# Drone.net
KiCad netlist of a schematic drawn in Altium Designer
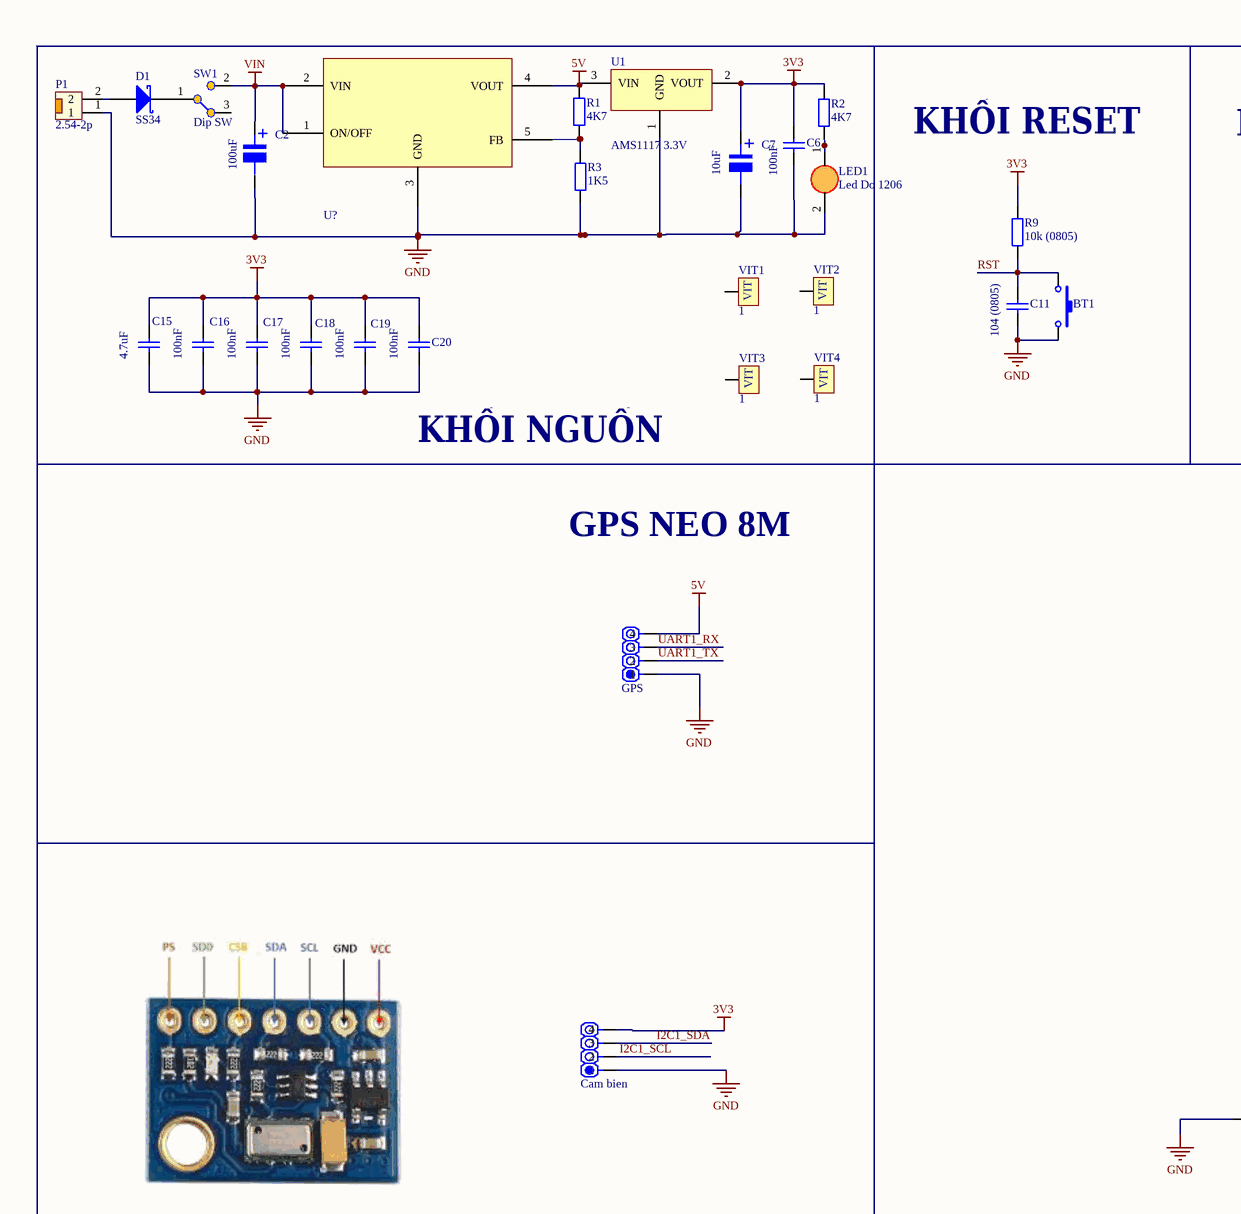
[diagram p0: Drone.SchDoc, top left]
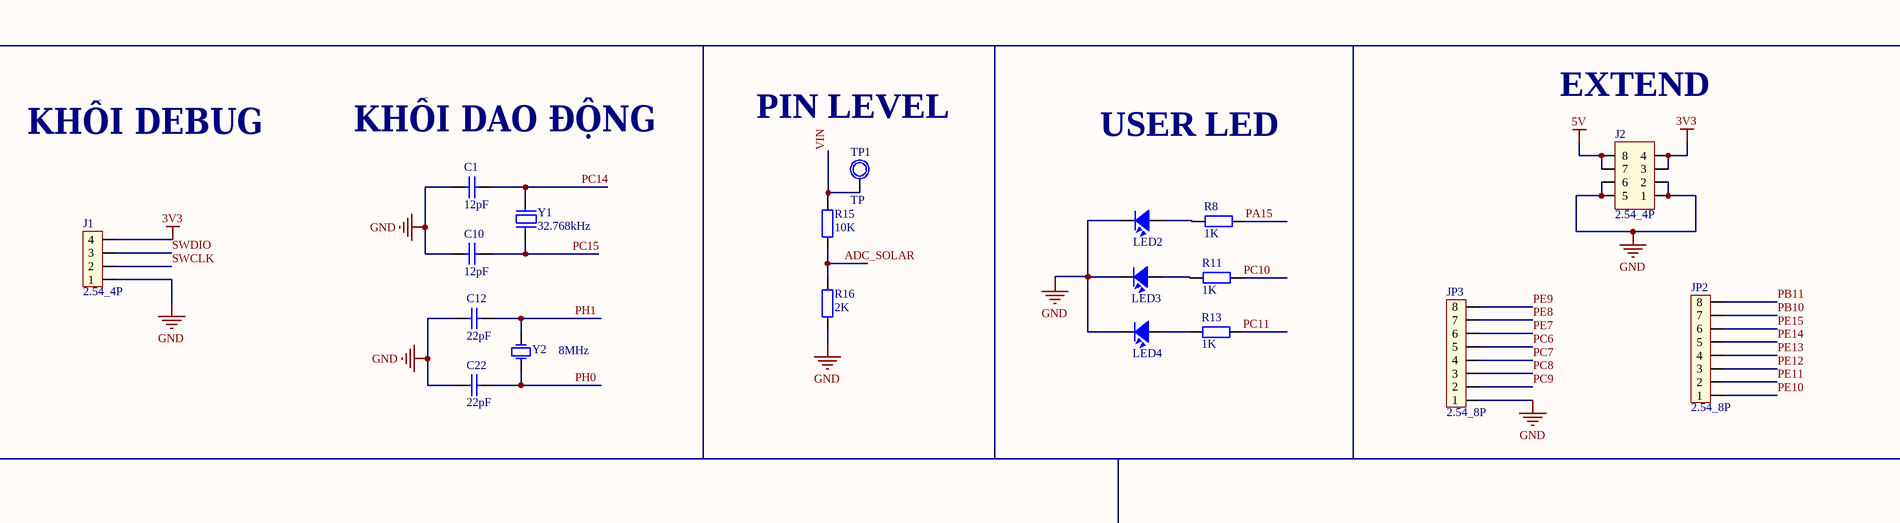
[diagram p1: Drone.SchDoc, top right]
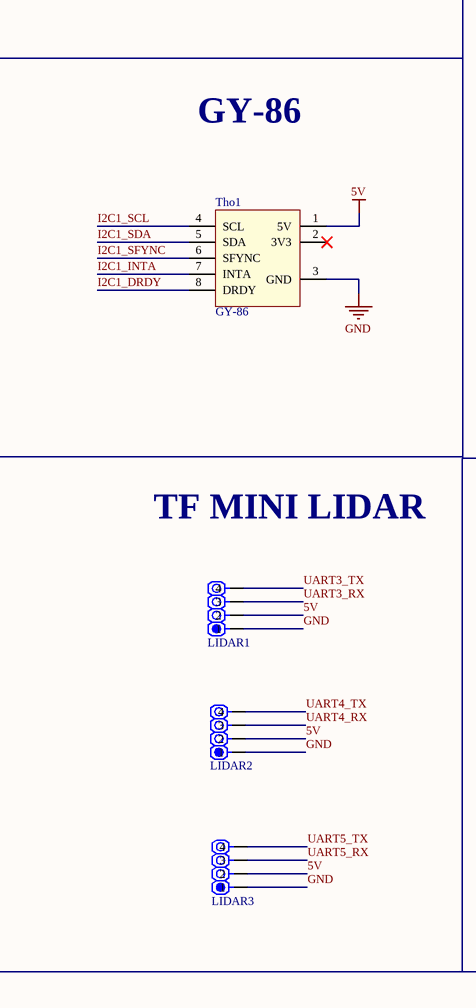
[diagram p2: Drone.SchDoc, bottom left]
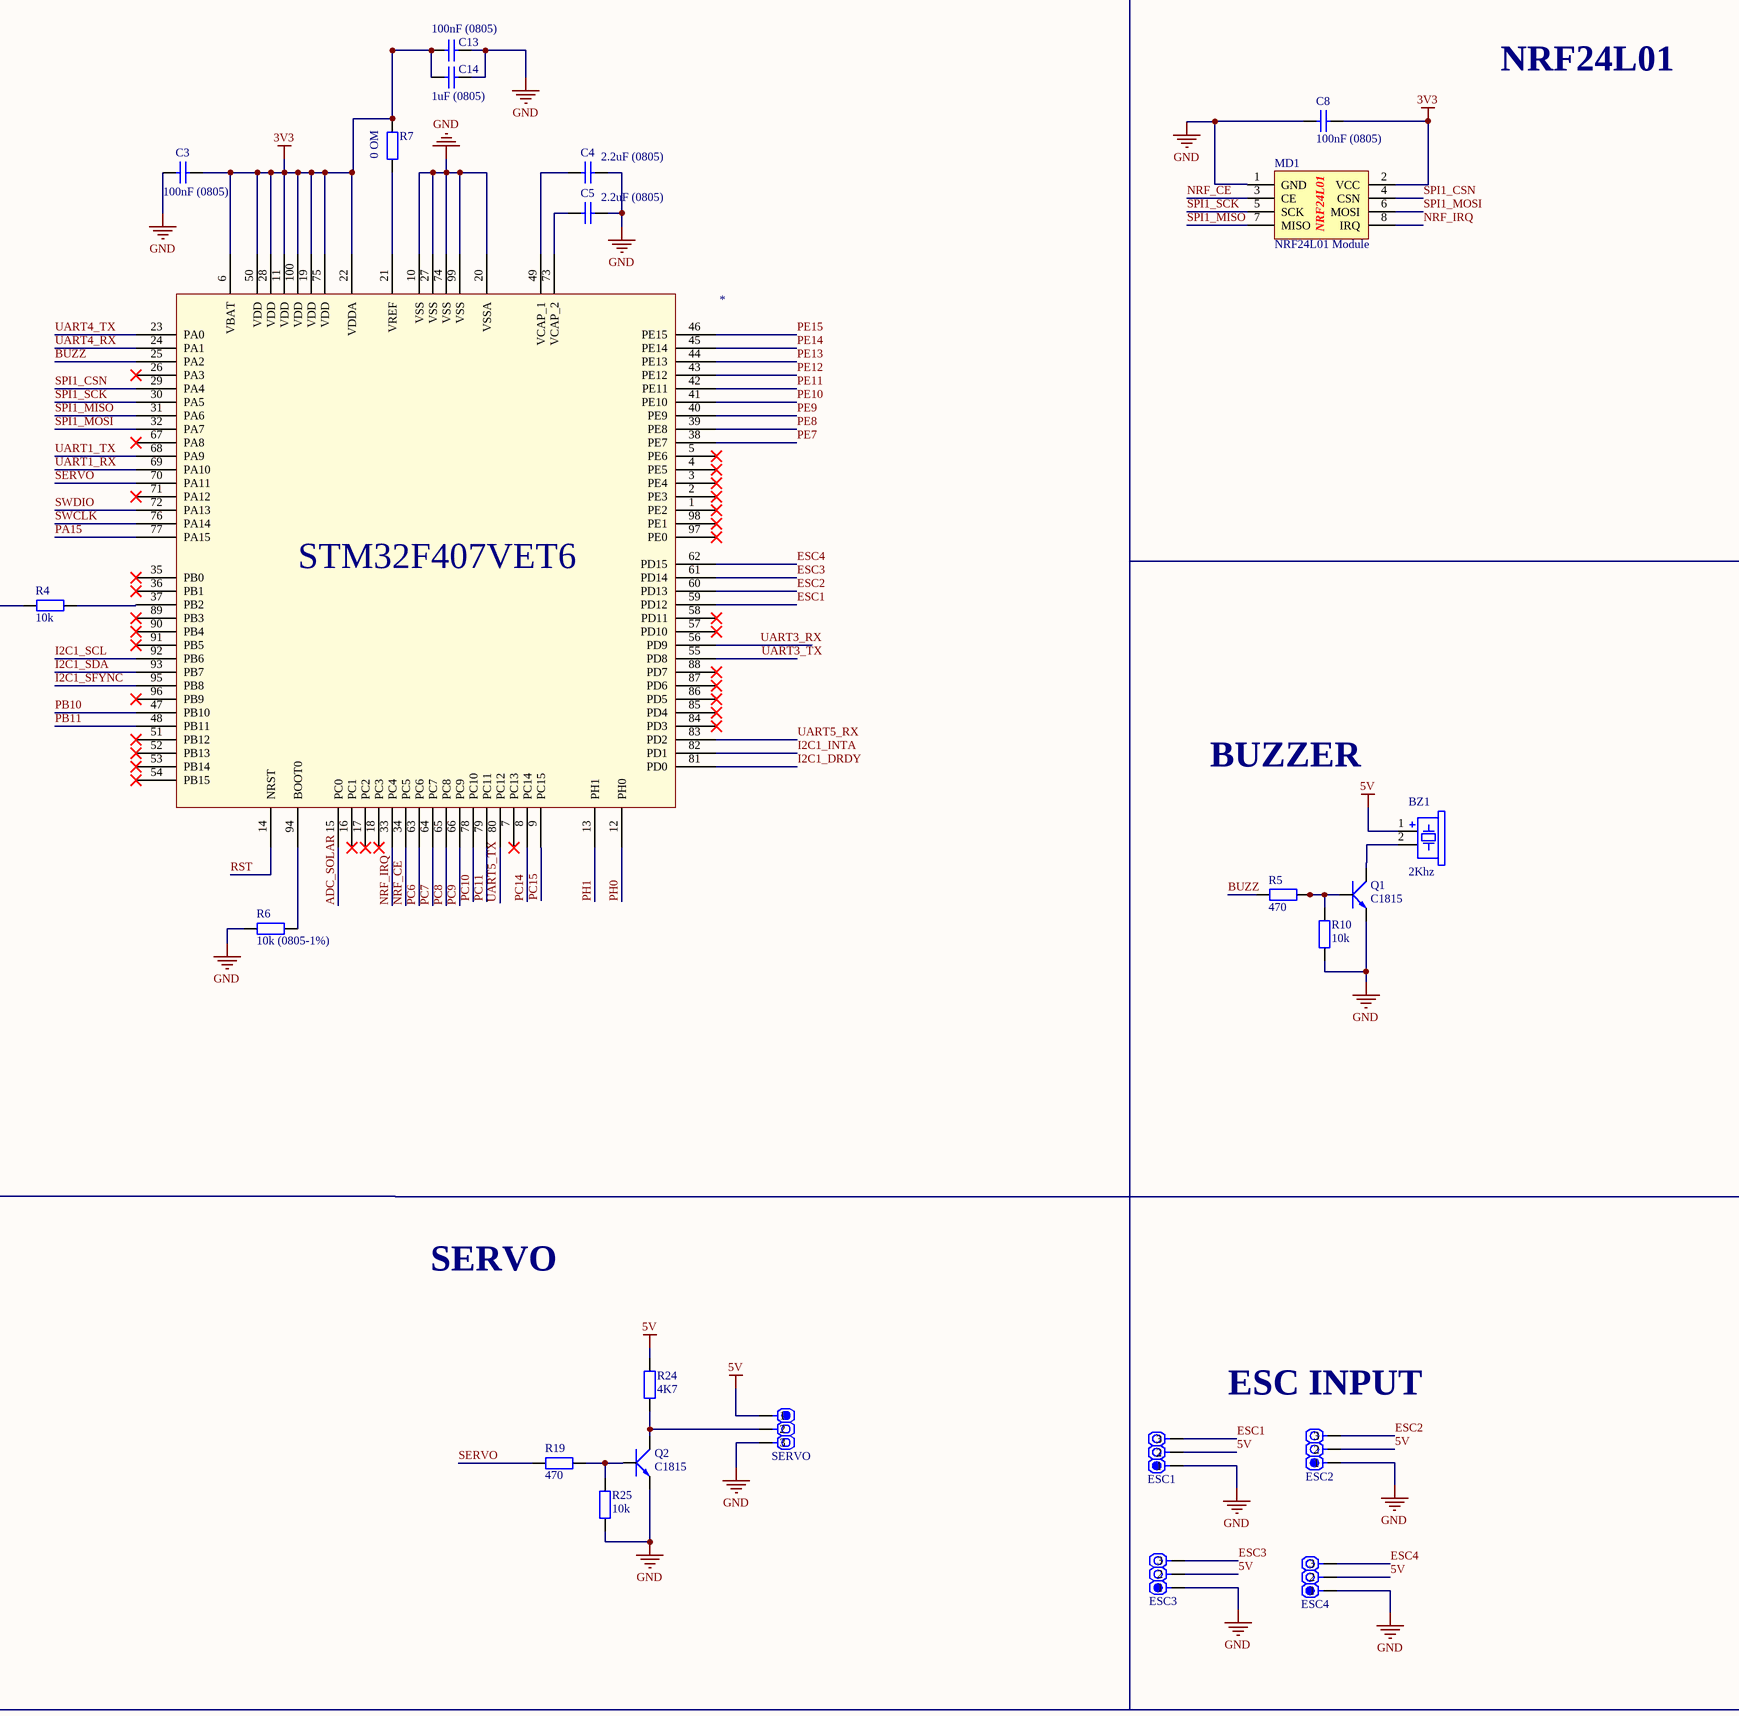
[diagram p3: Drone.SchDoc, bottom right]

(export (version "E")
  (design (tool "Eeschema 10.0.6"))
  (components
    (comp (ref "*")
      (value "STM32F407")
      (footprint "STM32F407Vet6")
      (libsource (lib "STM32f407") (part "STM32F407"))
    )
    (comp (ref "BT1")
      (value "Nút Nhấn 2 Chân 3x6x2.5MM SMD")
      (footprint "Nut Nhan 2 Chan SMD_N")
      (description "Dán")
      (libsource (lib "SCH Chuan") (part "Nut Nhan 2 Chan SMD"))
    )
    (comp (ref "BZ1")
      (value "2Khz")
      (footprint "coi xung")
      (description "Cắm")
      (libsource (lib "SCH Chuan") (part "Coi xung 2Khz"))
    )
    (comp (ref "C1")
      (value "12pF")
      (footprint "tu 0805")
      (description "Dán")
      (libsource (lib "SCH Chuan") (part "Tu 0805 10pF 50V 10%"))
    )
    (comp (ref "C2")
      (value "100uF")
      (footprint "tu nhom 10 (g)")
      (description "Dán")
      (libsource (lib "NhomLib") (part "Tu Nhom 100uF 35V"))
    )
    (comp (ref "C3")
      (value "100nF (0805)")
      (footprint "tu 0805")
      (description "Dán")
      (libsource (lib "SCH Chuan") (part "Tu 0805 220nF 50V 10%"))
    )
    (comp (ref "C4")
      (value "2.2uF (0805)")
      (footprint "tu 0805")
      (description "Dán")
      (libsource (lib "SCH Chuan") (part "Tu 0805 220nF 50V 10%"))
    )
    (comp (ref "C5")
      (value "2.2uF (0805)")
      (footprint "tu 0805")
      (description "Dán")
      (libsource (lib "SCH Chuan") (part "Tu 0805 220nF 50V 10%"))
    )
    (comp (ref "C6")
      (value "100nF")
      (footprint "tu 0805")
      (description "Dán")
      (libsource (lib "NhomLib") (part "Tu 0805 220nF 50V 10%"))
    )
    (comp (ref "C7")
      (value "10uF")
      (footprint "tu nhom 4 (b)")
      (description "Dán")
      (libsource (lib "NhomLib") (part "Tu Nhom 10uF 16V"))
    )
    (comp (ref "C8")
      (value "100nF (0805)")
      (footprint "tu 0805")
      (description "Dán")
      (libsource (lib "SCH Chuan") (part "Tu 0805 220nF 50V 10%"))
    )
    (comp (ref "C10")
      (value "12pF")
      (footprint "tu 0805")
      (description "Dán")
      (libsource (lib "SCH Chuan") (part "Tu 0805 10pF 50V 10%"))
    )
    (comp (ref "C11")
      (value "104 (0805)")
      (footprint "tu 0805")
      (description "Dán")
      (libsource (lib "SCH Chuan") (part "Tu 0805 104 50V 10%"))
    )
    (comp (ref "C12")
      (value "22pF")
      (footprint "tu 0805")
      (description "Dán")
      (libsource (lib "SCH Chuan") (part "Tu 0805 10pF 50V 10%"))
    )
    (comp (ref "C13")
      (value "100nF (0805)")
      (footprint "tu 0805")
      (description "Dán")
      (libsource (lib "SCH Chuan") (part "Tu 0805 220nF 50V 10%"))
    )
    (comp (ref "C14")
      (value "1uF (0805)")
      (footprint "tu 0805")
      (description "Dán")
      (libsource (lib "SCH Chuan") (part "Tu 0805 220nF 50V 10%"))
    )
    (comp (ref "C15")
      (value "4.7uF")
      (footprint "tu 0805")
      (description "Dán")
      (libsource (lib "SCH Chuan") (part "Tu 0805 104 50V 10%"))
    )
    (comp (ref "C16")
      (value "100nF")
      (footprint "tu 0805")
      (description "Dán")
      (libsource (lib "SCH Chuan") (part "Tu 0805 104 50V 10%"))
    )
    (comp (ref "C17")
      (value "100nF")
      (footprint "tu 0805")
      (description "Dán")
      (libsource (lib "SCH Chuan") (part "Tu 0805 104 50V 10%"))
    )
    (comp (ref "C18")
      (value "100nF")
      (footprint "tu 0805")
      (description "Dán")
      (libsource (lib "SCH Chuan") (part "Tu 0805 104 50V 10%"))
    )
    (comp (ref "C19")
      (value "100nF")
      (footprint "tu 0805")
      (description "Dán")
      (libsource (lib "SCH Chuan") (part "Tu 0805 104 50V 10%"))
    )
    (comp (ref "C20")
      (value "100nF")
      (footprint "tu 0805")
      (description "Dán")
      (libsource (lib "SCH Chuan") (part "Tu 0805 104 50V 10%"))
    )
    (comp (ref "C22")
      (value "22pF")
      (footprint "tu 0805")
      (description "Dán")
      (libsource (lib "SCH Chuan") (part "Tu 0805 10pF 50V 10%"))
    )
    (comp (ref "Cam bien")
      (value "IO")
      (footprint "CON.HDR1X4L")
      (description "Header 1x4")
      (fields (field (name "PUBLISHER") "NKIM"))
      (libsource (lib "VPMyLibrary") (part "CON.HDR1x4"))
    )
    (comp (ref "D1")
      (value "SS34")
      (footprint "DIODE_DO214AC_SMA")
      (description "DIODE SCHOTTKY 40V 3A SMA")
      (libsource (lib "NhomLib") (part "SS34"))
    )
    (comp (ref "ESC1")
      (value "IO")
      (footprint "CON.HDR1X3")
      (description "Header 1x3")
      (fields (field (name "PUBLISHER") "NKIM"))
      (libsource (lib "VPMyLibrary") (part "CON.HDR1x3"))
    )
    (comp (ref "ESC2")
      (value "IO")
      (footprint "CON.HDR1X3")
      (description "Header 1x3")
      (fields (field (name "PUBLISHER") "NKIM"))
      (libsource (lib "VPMyLibrary") (part "CON.HDR1x3"))
    )
    (comp (ref "ESC3")
      (value "IO")
      (footprint "CON.HDR1X3")
      (description "Header 1x3")
      (fields (field (name "PUBLISHER") "NKIM"))
      (libsource (lib "VPMyLibrary") (part "CON.HDR1x3"))
    )
    (comp (ref "ESC4")
      (value "IO")
      (footprint "CON.HDR1X3")
      (description "Header 1x3")
      (fields (field (name "PUBLISHER") "NKIM"))
      (libsource (lib "VPMyLibrary") (part "CON.HDR1x3"))
    )
    (comp (ref "GPS")
      (value "IO")
      (footprint "CON.HDR1X4L")
      (description "Header 1x4")
      (fields (field (name "PUBLISHER") "NKIM"))
      (libsource (lib "VPMyLibrary") (part "CON.HDR1x4"))
    )
    (comp (ref "J1")
      (value "2.54_4P")
      (footprint "jump don duc thang 2.54_4p")
      (description "Cắm")
      (libsource (lib "NhomLib") (part "Jump Don Duc Thang 2.54_4P"))
    )
    (comp (ref "J2")
      (value "2.54_4P")
      (footprint "JP4x2")
      (description "Cắm")
      (libsource (lib "NhomLib") (part "Jump Doi Duc 2.54_4Px2"))
    )
    (comp (ref "JP2")
      (value "2.54_8P")
      (footprint "Jump Don Duc Thang 2.54_8p")
      (description "Cắm")
      (libsource (lib "NhomLib") (part "Jump Don Duc 2.54_8P"))
    )
    (comp (ref "JP3")
      (value "2.54_8P")
      (footprint "Jump Don Duc Thang 2.54_8p")
      (description "Cắm")
      (libsource (lib "NhomLib") (part "Jump Don Duc 2.54_8P"))
    )
    (comp (ref "LED1")
      (value "Led Do 1206")
      (footprint "led 1206")
      (description "Dán")
      (libsource (lib "NhomLib") (part "Led 1206 Do"))
    )
    (comp (ref "LED2")
      (value "LED SMD")
      (footprint "SM-LED-0805-Yellow")
      (libsource (lib "syhaunguyen") (part "LED-SMD-0805"))
    )
    (comp (ref "LED3")
      (value "LED SMD")
      (footprint "SM-LED-0805-Green")
      (libsource (lib "syhaunguyen") (part "LED-SMD-0805"))
    )
    (comp (ref "LED4")
      (value "LED SMD")
      (footprint "SM-LED-0805-Blue")
      (libsource (lib "syhaunguyen") (part "LED-SMD-0805"))
    )
    (comp (ref "LIDAR1")
      (value "IO")
      (footprint "CON.HDR1X4L")
      (description "Header 1x4")
      (fields (field (name "PUBLISHER") "NKIM"))
      (libsource (lib "VPMyLibrary") (part "CON.HDR1x4"))
    )
    (comp (ref "LIDAR2")
      (value "IO")
      (footprint "CON.HDR1X4L")
      (description "Header 1x4")
      (fields (field (name "PUBLISHER") "NKIM"))
      (libsource (lib "VPMyLibrary") (part "CON.HDR1x4"))
    )
    (comp (ref "LIDAR3")
      (value "IO")
      (footprint "CON.HDR1X4L")
      (description "Header 1x4")
      (fields (field (name "PUBLISHER") "NKIM"))
      (libsource (lib "VPMyLibrary") (part "CON.HDR1x4"))
    )
    (comp (ref "MD1")
      (value "NRF24L01 Module")
      (footprint "NRF24L01")
      (libsource (lib "Altium_Lib_by_KhueNguyenCreator") (part "NRF24L01 Module"))
    )
    (comp (ref "MIC1")
      (value "U?")
      (footprint "Mic5V")
      (description "3A")
      (libsource (lib "node_mcu") (part "Mic5V"))
    )
    (comp (ref "P1")
      (value "2.54-2p")
      (footprint "Header Duc Thang 2P 2.54")
      (description "Cắm")
      (libsource (lib "NhomLib") (part "Header 2.54-2p Duc Thang"))
    )
    (comp (ref "Q1")
      (value "C1815")
      (footprint "SOT23B")
      (description "NPN 600mW, ECB")
      (libsource (lib "syhaunguyen") (part "C1815"))
    )
    (comp (ref "Q2")
      (value "C1815")
      (footprint "SOT23B")
      (description "NPN 600mW, ECB")
      (libsource (lib "syhaunguyen") (part "C1815"))
    )
    (comp (ref "R1")
      (value "4K7")
      (footprint "tro 0805")
      (description "Dán")
      (libsource (lib "SCH Chuan") (part "Tro 0805 5% 10k"))
    )
    (comp (ref "R2")
      (value "4K7")
      (footprint "tro 0805")
      (description "Dán")
      (libsource (lib "SCH Chuan") (part "Tro 0805 5% 10k"))
    )
    (comp (ref "R3")
      (value "1K5")
      (footprint "tro 0805")
      (description "Dán")
      (libsource (lib "SCH Chuan") (part "Tro 0805 5% 10k"))
    )
    (comp (ref "R4")
      (value "10k")
      (footprint "tro 0805")
      (description "Dán")
      (libsource (lib "SCH Chuan") (part "Tro 0805 1% 10k"))
    )
    (comp (ref "R5")
      (value "470")
      (footprint "tro 0805")
      (description "Dán")
      (libsource (lib "SCH Chuan") (part "Tro 0805 1% 10k"))
    )
    (comp (ref "R6")
      (value "10k (0805-1%)")
      (footprint "tro 0805")
      (description "Dán")
      (libsource (lib "SCH Chuan") (part "Tro 0805 1% 10k"))
    )
    (comp (ref "R7")
      (value "0 OM")
      (footprint "tro 0805")
      (description "Dán")
      (libsource (lib "SCH Chuan") (part "Tro 0805 5% 10k"))
    )
    (comp (ref "R8")
      (value "1K")
      (footprint "tro 0805")
      (description "Dán")
      (libsource (lib "SCH Chuan") (part "Tro 0805 5% 470R"))
    )
    (comp (ref "R9")
      (value "10k (0805)")
      (footprint "tro 0805")
      (description "Dán")
      (libsource (lib "SCH Chuan") (part "Tro 0805 5% 10k"))
    )
    (comp (ref "R10")
      (value "10k")
      (footprint "tro 0805")
      (description "Dán")
      (libsource (lib "SCH Chuan") (part "Tro 0805 1% 10k"))
    )
    (comp (ref "R11")
      (value "1K")
      (footprint "tro 0805")
      (description "Dán")
      (libsource (lib "SCH Chuan") (part "Tro 0805 5% 470R"))
    )
    (comp (ref "R13")
      (value "1K")
      (footprint "tro 0805")
      (description "Dán")
      (libsource (lib "SCH Chuan") (part "Tro 0805 5% 470R"))
    )
    (comp (ref "R15")
      (value "10K")
      (footprint "tro 0805")
      (description "Dán")
      (libsource (lib "SCH Chuan") (part "Tro 0805 5% 10k"))
    )
    (comp (ref "R16")
      (value "2K")
      (footprint "tro 0805")
      (description "Dán")
      (libsource (lib "SCH Chuan") (part "Tro 0805 5% 10k"))
    )
    (comp (ref "R19")
      (value "470")
      (footprint "tro 0805")
      (description "Dán")
      (libsource (lib "SCH Chuan") (part "Tro 0805 1% 10k"))
    )
    (comp (ref "R24")
      (value "4K7")
      (footprint "tro 0805")
      (description "Dán")
      (libsource (lib "SCH Chuan") (part "Tro 0805 1% 10k"))
    )
    (comp (ref "R25")
      (value "10k")
      (footprint "tro 0805")
      (description "Dán")
      (libsource (lib "SCH Chuan") (part "Tro 0805 1% 10k"))
    )
    (comp (ref "SERVO")
      (value "IO")
      (footprint "CON.HDR1X3")
      (description "Header 1x3")
      (fields (field (name "PUBLISHER") "NKIM"))
      (libsource (lib "VPMyLibrary") (part "CON.HDR1x3"))
    )
    (comp (ref "SW1")
      (value "Dip SW")
      (footprint "SW3P")
      (description "Dip Switch 3 pin")
      (libsource (lib "VPMyLibrary") (part "Switch3P"))
    )
    (comp (ref "Tho1") (value "GY-86") (footprint "GY-86") (libsource (lib "JOYSTICK") (part "GY-86")))
    (comp (ref "TP1")
      (value "TP")
      (footprint "TP1")
      (description "Test Point")
      (libsource (lib "syhaunguyen") (part "TP1"))
    )
    (comp (ref "U1")
      (value "AMS1117 3.3V")
      (footprint "SOT223")
      (description "Dán")
      (libsource (lib "NhomLib") (part "AMS1117 3.3V"))
    )
    (comp (ref "VIT1")
      (value "1")
      (footprint "VIT")
      (description "Oc Vit")
      (libsource (lib "NhomLib") (part "VIT"))
    )
    (comp (ref "VIT2")
      (value "1")
      (footprint "VIT")
      (description "Oc Vit")
      (libsource (lib "NhomLib") (part "VIT"))
    )
    (comp (ref "VIT3")
      (value "1")
      (footprint "VIT")
      (description "Oc Vit")
      (libsource (lib "NhomLib") (part "VIT"))
    )
    (comp (ref "VIT4")
      (value "1")
      (footprint "VIT")
      (description "Oc Vit")
      (libsource (lib "NhomLib") (part "VIT"))
    )
    (comp (ref "Y1")
      (value "32.768kHz")
      (footprint "Thach Anh 2 Chan 32,768 KHz")
      (description "Crystal For all Crystal 2pin.")
      (libsource (lib "Altium_Lib_by_KhueNguyenCreator") (part "Thach Anh 2 chan 32,768 Khz"))
    )
    (comp (ref "Y2")
      (value "8MHz")
      (footprint "thach anh 49s smd")
      (description "Dán")
      (libsource (lib "SCH Chuan") (part "Thach anh 8MHz 49S SMD"))
    )
  )
  (nets
    (net (code "1") (name "/ADC_SOLAR") (class "Default")
      (node (ref "*") (pin "15") (pinfunction "PC0_15") (pintype "passive"))
      (node (ref "R15") (pin "1") (pinfunction "1_1") (pintype "passive"))
      (node (ref "R16") (pin "2") (pinfunction "2_2") (pintype "passive"))
    )
    (net (code "2") (name "/BUZZ") (class "Default")
      (node (ref "*") (pin "25") (pinfunction "PA2_25") (pintype "passive"))
      (node (ref "R5") (pin "2") (pinfunction "2_2") (pintype "passive"))
    )
    (net (code "3") (name "/ESC1") (class "Default")
      (node (ref "*") (pin "59") (pinfunction "PD12_59") (pintype "passive"))
      (node (ref "ESC1") (pin "3") (pinfunction "3_3") (pintype "passive"))
    )
    (net (code "4") (name "/ESC2") (class "Default")
      (node (ref "*") (pin "60") (pinfunction "PD13_60") (pintype "passive"))
      (node (ref "ESC2") (pin "3") (pinfunction "3_3") (pintype "passive"))
    )
    (net (code "5") (name "/ESC3") (class "Default")
      (node (ref "*") (pin "61") (pinfunction "PD14_61") (pintype "passive"))
      (node (ref "ESC3") (pin "3") (pinfunction "3_3") (pintype "passive"))
    )
    (net (code "6") (name "/ESC4") (class "Default")
      (node (ref "*") (pin "62") (pinfunction "PD15_62") (pintype "passive"))
      (node (ref "ESC4") (pin "3") (pinfunction "3_3") (pintype "passive"))
    )
    (net (code "7") (name "/I2C1_DRDY") (class "Default")
      (node (ref "*") (pin "81") (pinfunction "PD0_81") (pintype "passive"))
      (node (ref "Tho1") (pin "8") (pinfunction "DRDY_8") (pintype "passive"))
    )
    (net (code "8") (name "/I2C1_INTA") (class "Default")
      (node (ref "*") (pin "82") (pinfunction "PD1_82") (pintype "passive"))
      (node (ref "Tho1") (pin "7") (pinfunction "INTA_7") (pintype "passive"))
    )
    (net (code "9") (name "/I2C1_SCL") (class "Default")
      (node (ref "*") (pin "92") (pinfunction "PB6_92") (pintype "passive"))
      (node (ref "Cam bien") (pin "2") (pinfunction "2_2") (pintype "passive"))
      (node (ref "Tho1") (pin "4") (pinfunction "SCL_4") (pintype "passive"))
    )
    (net (code "10") (name "/I2C1_SDA") (class "Default")
      (node (ref "*") (pin "93") (pinfunction "PB7_93") (pintype "passive"))
      (node (ref "Cam bien") (pin "3") (pinfunction "3_3") (pintype "passive"))
      (node (ref "Tho1") (pin "5") (pinfunction "SDA_5") (pintype "passive"))
    )
    (net (code "11") (name "/I2C1_SFYNC") (class "Default")
      (node (ref "*") (pin "95") (pinfunction "PB8_95") (pintype "passive"))
      (node (ref "Tho1") (pin "6") (pinfunction "SFYNC_6") (pintype "passive"))
    )
    (net (code "12") (name "/NRF_CE") (class "Default")
      (node (ref "*") (pin "34") (pinfunction "PC5_34") (pintype "passive"))
      (node (ref "MD1") (pin "3") (pinfunction "CE_3") (pintype "passive"))
    )
    (net (code "13") (name "/NRF_IRQ") (class "Default")
      (node (ref "*") (pin "33") (pinfunction "PC4_33") (pintype "passive"))
      (node (ref "MD1") (pin "8") (pinfunction "IRQ_8") (pintype "passive"))
    )
    (net (code "14") (name "/PA15") (class "Default")
      (node (ref "*") (pin "77") (pinfunction "PA15_77") (pintype "passive"))
      (node (ref "R8") (pin "2") (pinfunction "2_2") (pintype "passive"))
    )
    (net (code "15") (name "/PB10") (class "Default")
      (node (ref "*") (pin "47") (pinfunction "PB10_47") (pintype "passive"))
      (node (ref "JP2") (pin "7") (pinfunction "7_7") (pintype "passive"))
    )
    (net (code "16") (name "/PB11") (class "Default")
      (node (ref "*") (pin "48") (pinfunction "PB11_48") (pintype "passive"))
      (node (ref "JP2") (pin "8") (pinfunction "8_8") (pintype "passive"))
    )
    (net (code "17") (name "/PC6") (class "Default")
      (node (ref "*") (pin "63") (pinfunction "PC6_63") (pintype "passive"))
      (node (ref "JP3") (pin "5") (pinfunction "5_5") (pintype "passive"))
    )
    (net (code "18") (name "/PC7") (class "Default")
      (node (ref "*") (pin "64") (pinfunction "PC7_64") (pintype "passive"))
      (node (ref "JP3") (pin "4") (pinfunction "4_4") (pintype "passive"))
    )
    (net (code "19") (name "/PC8") (class "Default")
      (node (ref "*") (pin "65") (pinfunction "PC8_65") (pintype "passive"))
      (node (ref "JP3") (pin "3") (pinfunction "3_3") (pintype "passive"))
    )
    (net (code "20") (name "/PC9") (class "Default")
      (node (ref "*") (pin "66") (pinfunction "PC9_66") (pintype "passive"))
      (node (ref "JP3") (pin "2") (pinfunction "2_2") (pintype "passive"))
    )
    (net (code "21") (name "/PC10") (class "Default")
      (node (ref "*") (pin "78") (pinfunction "PC10_78") (pintype "passive"))
      (node (ref "R11") (pin "2") (pinfunction "2_2") (pintype "passive"))
    )
    (net (code "22") (name "/PC11") (class "Default")
      (node (ref "*") (pin "79") (pinfunction "PC11_79") (pintype "passive"))
      (node (ref "R13") (pin "2") (pinfunction "2_2") (pintype "passive"))
    )
    (net (code "23") (name "/PC14") (class "Default")
      (node (ref "*") (pin "8") (pinfunction "PC14_8") (pintype "passive"))
      (node (ref "C1") (pin "1") (pinfunction "1_1") (pintype "passive"))
      (node (ref "Y1") (pin "2") (pinfunction "2_2") (pintype "passive"))
    )
    (net (code "24") (name "/PC15") (class "Default")
      (node (ref "*") (pin "9") (pinfunction "PC15_9") (pintype "passive"))
      (node (ref "C10") (pin "1") (pinfunction "1_1") (pintype "passive"))
      (node (ref "Y1") (pin "1") (pinfunction "1_1") (pintype "passive"))
    )
    (net (code "25") (name "/PE7") (class "Default")
      (node (ref "*") (pin "38") (pinfunction "PE7_38") (pintype "passive"))
      (node (ref "JP3") (pin "6") (pinfunction "6_6") (pintype "passive"))
    )
    (net (code "26") (name "/PE8") (class "Default")
      (node (ref "*") (pin "39") (pinfunction "PE8_39") (pintype "passive"))
      (node (ref "JP3") (pin "7") (pinfunction "7_7") (pintype "passive"))
    )
    (net (code "27") (name "/PE9") (class "Default")
      (node (ref "*") (pin "40") (pinfunction "PE9_40") (pintype "passive"))
      (node (ref "JP3") (pin "8") (pinfunction "8_8") (pintype "passive"))
    )
    (net (code "28") (name "/PE10") (class "Default")
      (node (ref "*") (pin "41") (pinfunction "PE10_41") (pintype "passive"))
      (node (ref "JP2") (pin "1") (pinfunction "1_1") (pintype "passive"))
    )
    (net (code "29") (name "/PE11") (class "Default")
      (node (ref "*") (pin "42") (pinfunction "PE11_42") (pintype "passive"))
      (node (ref "JP2") (pin "2") (pinfunction "2_2") (pintype "passive"))
    )
    (net (code "30") (name "/PE12") (class "Default")
      (node (ref "*") (pin "43") (pinfunction "PE12_43") (pintype "passive"))
      (node (ref "JP2") (pin "3") (pinfunction "3_3") (pintype "passive"))
    )
    (net (code "31") (name "/PE13") (class "Default")
      (node (ref "*") (pin "44") (pinfunction "PE13_44") (pintype "passive"))
      (node (ref "JP2") (pin "4") (pinfunction "4_4") (pintype "passive"))
    )
    (net (code "32") (name "/PE14") (class "Default")
      (node (ref "*") (pin "45") (pinfunction "PE14_45") (pintype "passive"))
      (node (ref "JP2") (pin "5") (pinfunction "5_5") (pintype "passive"))
    )
    (net (code "33") (name "/PE15") (class "Default")
      (node (ref "*") (pin "46") (pinfunction "PE15_46") (pintype "passive"))
      (node (ref "JP2") (pin "6") (pinfunction "6_6") (pintype "passive"))
    )
    (net (code "34") (name "/PH0") (class "Default")
      (node (ref "*") (pin "12") (pinfunction "PH0_12") (pintype "passive"))
      (node (ref "C22") (pin "1") (pinfunction "1_1") (pintype "passive"))
      (node (ref "Y2") (pin "2") (pinfunction "OSC2_2") (pintype "passive"))
    )
    (net (code "35") (name "/PH1") (class "Default")
      (node (ref "*") (pin "13") (pinfunction "PH1_13") (pintype "passive"))
      (node (ref "C12") (pin "1") (pinfunction "1_1") (pintype "passive"))
      (node (ref "Y2") (pin "1") (pinfunction "OSC1_1") (pintype "passive"))
    )
    (net (code "36") (name "/RST") (class "Default")
      (node (ref "*") (pin "14") (pinfunction "NRST_14") (pintype "passive"))
      (node (ref "BT1") (pin "1") (pinfunction "1_1") (pintype "passive"))
      (node (ref "C11") (pin "1") (pinfunction "1_1") (pintype "passive"))
      (node (ref "R9") (pin "1") (pinfunction "1_1") (pintype "passive"))
    )
    (net (code "37") (name "/SERVO") (class "Default")
      (node (ref "*") (pin "70") (pinfunction "PA11_70") (pintype "passive"))
      (node (ref "R19") (pin "2") (pinfunction "2_2") (pintype "passive"))
    )
    (net (code "38") (name "/SPI1_CSN") (class "Default")
      (node (ref "*") (pin "29") (pinfunction "PA4_29") (pintype "passive"))
      (node (ref "MD1") (pin "4") (pinfunction "CSN_4") (pintype "passive"))
    )
    (net (code "39") (name "/SPI1_MISO") (class "Default")
      (node (ref "*") (pin "31") (pinfunction "PA6_31") (pintype "passive"))
      (node (ref "MD1") (pin "7") (pinfunction "MISO_7") (pintype "passive"))
    )
    (net (code "40") (name "/SPI1_MOSI") (class "Default")
      (node (ref "*") (pin "32") (pinfunction "PA7_32") (pintype "passive"))
      (node (ref "MD1") (pin "6") (pinfunction "MOSI_6") (pintype "passive"))
    )
    (net (code "41") (name "/SPI1_SCK") (class "Default")
      (node (ref "*") (pin "30") (pinfunction "PA5_30") (pintype "passive"))
      (node (ref "MD1") (pin "5") (pinfunction "SCK_5") (pintype "passive"))
    )
    (net (code "42") (name "/SWCLK") (class "Default")
      (node (ref "*") (pin "76") (pinfunction "PA14_76") (pintype "passive"))
      (node (ref "J1") (pin "2") (pinfunction "2_2") (pintype "passive"))
    )
    (net (code "43") (name "/SWDIO") (class "Default")
      (node (ref "*") (pin "72") (pinfunction "PA13_72") (pintype "passive"))
      (node (ref "J1") (pin "3") (pinfunction "3_3") (pintype "passive"))
    )
    (net (code "44") (name "/UART1_RX") (class "Default")
      (node (ref "*") (pin "69") (pinfunction "PA10_69") (pintype "passive"))
      (node (ref "GPS") (pin "3") (pinfunction "3_3") (pintype "passive"))
    )
    (net (code "45") (name "/UART1_TX") (class "Default")
      (node (ref "*") (pin "68") (pinfunction "PA9_68") (pintype "passive"))
      (node (ref "GPS") (pin "2") (pinfunction "2_2") (pintype "passive"))
    )
    (net (code "46") (name "/UART3_RX") (class "Default")
      (node (ref "*") (pin "56") (pinfunction "PD9_56") (pintype "passive"))
      (node (ref "LIDAR1") (pin "3") (pinfunction "3_3") (pintype "passive"))
    )
    (net (code "47") (name "/UART3_TX") (class "Default")
      (node (ref "*") (pin "55") (pinfunction "PD8_55") (pintype "passive"))
      (node (ref "LIDAR1") (pin "4") (pinfunction "4_4") (pintype "passive"))
    )
    (net (code "48") (name "/UART4_RX") (class "Default")
      (node (ref "*") (pin "24") (pinfunction "PA1_24") (pintype "passive"))
      (node (ref "LIDAR2") (pin "3") (pinfunction "3_3") (pintype "passive"))
    )
    (net (code "49") (name "/UART4_TX") (class "Default")
      (node (ref "*") (pin "23") (pinfunction "PA0_23") (pintype "passive"))
      (node (ref "LIDAR2") (pin "4") (pinfunction "4_4") (pintype "passive"))
    )
    (net (code "50") (name "/UART5_RX") (class "Default")
      (node (ref "*") (pin "83") (pinfunction "PD2_83") (pintype "passive"))
      (node (ref "LIDAR3") (pin "3") (pinfunction "3_3") (pintype "passive"))
    )
    (net (code "51") (name "/UART5_TX") (class "Default")
      (node (ref "*") (pin "80") (pinfunction "PC12_80") (pintype "passive"))
      (node (ref "LIDAR3") (pin "4") (pinfunction "4_4") (pintype "passive"))
    )
    (net (code "52") (name "3V3") (class "Default")
      (node (ref "*") (pin "100") (pinfunction "VDD_100") (pintype "passive"))
      (node (ref "*") (pin "11") (pinfunction "VDD_11") (pintype "passive"))
      (node (ref "*") (pin "19") (pinfunction "VDD_19") (pintype "passive"))
      (node (ref "*") (pin "22") (pinfunction "VDDA_22") (pintype "passive"))
      (node (ref "*") (pin "28") (pinfunction "VDD_28") (pintype "passive"))
      (node (ref "*") (pin "50") (pinfunction "VDD_50") (pintype "passive"))
      (node (ref "*") (pin "6") (pinfunction "VBAT_6") (pintype "passive"))
      (node (ref "*") (pin "75") (pinfunction "VDD_75") (pintype "passive"))
      (node (ref "C13") (pin "2") (pinfunction "2_2") (pintype "passive"))
      (node (ref "C14") (pin "2") (pinfunction "2_2") (pintype "passive"))
      (node (ref "C15") (pin "1") (pinfunction "1_1") (pintype "passive"))
      (node (ref "C16") (pin "1") (pinfunction "1_1") (pintype "passive"))
      (node (ref "C17") (pin "1") (pinfunction "1_1") (pintype "passive"))
      (node (ref "C18") (pin "1") (pinfunction "1_1") (pintype "passive"))
      (node (ref "C19") (pin "1") (pinfunction "1_1") (pintype "passive"))
      (node (ref "C20") (pin "1") (pinfunction "1_1") (pintype "passive"))
      (node (ref "C3") (pin "1") (pinfunction "1_1") (pintype "passive"))
      (node (ref "C6") (pin "1") (pinfunction "1_1") (pintype "passive"))
      (node (ref "C7") (pin "1") (pinfunction "1_1") (pintype "passive"))
      (node (ref "C8") (pin "2") (pinfunction "2_2") (pintype "passive"))
      (node (ref "Cam bien") (pin "4") (pinfunction "4_4") (pintype "passive"))
      (node (ref "J1") (pin "4") (pinfunction "4_4") (pintype "passive"))
      (node (ref "J2") (pin "3") (pinfunction "3_3") (pintype "passive"))
      (node (ref "J2") (pin "4") (pinfunction "4_4") (pintype "passive"))
      (node (ref "MD1") (pin "2") (pinfunction "VCC_2") (pintype "passive"))
      (node (ref "R2") (pin "1") (pinfunction "1_1") (pintype "passive"))
      (node (ref "R7") (pin "2") (pinfunction "2_2") (pintype "passive"))
      (node (ref "R9") (pin "2") (pinfunction "2_2") (pintype "passive"))
      (node (ref "U1") (pin "2") (pinfunction "VOUT_2") (pintype "passive"))
    )
    (net (code "53") (name "5V") (class "Default")
      (node (ref "BZ1") (pin "1") (pinfunction "1_1") (pintype "passive"))
      (node (ref "ESC1") (pin "2") (pinfunction "2_2") (pintype "passive"))
      (node (ref "ESC2") (pin "2") (pinfunction "2_2") (pintype "passive"))
      (node (ref "ESC3") (pin "2") (pinfunction "2_2") (pintype "passive"))
      (node (ref "ESC4") (pin "2") (pinfunction "2_2") (pintype "passive"))
      (node (ref "GPS") (pin "4") (pinfunction "4_4") (pintype "passive"))
      (node (ref "J2") (pin "7") (pinfunction "7_7") (pintype "passive"))
      (node (ref "J2") (pin "8") (pinfunction "8_8") (pintype "passive"))
      (node (ref "LIDAR1") (pin "2") (pinfunction "2_2") (pintype "passive"))
      (node (ref "LIDAR2") (pin "2") (pinfunction "2_2") (pintype "passive"))
      (node (ref "LIDAR3") (pin "2") (pinfunction "2_2") (pintype "passive"))
      (node (ref "MIC1") (pin "4") (pinfunction "VOUT_4") (pintype "passive"))
      (node (ref "R1") (pin "2") (pinfunction "2_2") (pintype "passive"))
      (node (ref "R24") (pin "2") (pinfunction "2_2") (pintype "passive"))
      (node (ref "SERVO") (pin "1") (pinfunction "1_1") (pintype "passive"))
      (node (ref "Tho1") (pin "1") (pinfunction "5V_1") (pintype "passive"))
      (node (ref "U1") (pin "3") (pinfunction "VIN_3") (pintype "passive"))
    )
    (net (code "54") (name "GND") (class "Default")
      (node (ref "*") (pin "10") (pinfunction "VSS_10") (pintype "passive"))
      (node (ref "*") (pin "20") (pinfunction "VSSA_20") (pintype "passive"))
      (node (ref "*") (pin "27") (pinfunction "VSS_27") (pintype "passive"))
      (node (ref "*") (pin "74") (pinfunction "VSS_74") (pintype "passive"))
      (node (ref "*") (pin "99") (pinfunction "VSS_99") (pintype "passive"))
      (node (ref "BT1") (pin "2") (pinfunction "2_2") (pintype "passive"))
      (node (ref "C1") (pin "2") (pinfunction "2_2") (pintype "passive"))
      (node (ref "C10") (pin "2") (pinfunction "2_2") (pintype "passive"))
      (node (ref "C11") (pin "2") (pinfunction "2_2") (pintype "passive"))
      (node (ref "C12") (pin "2") (pinfunction "2_2") (pintype "passive"))
      (node (ref "C13") (pin "1") (pinfunction "1_1") (pintype "passive"))
      (node (ref "C14") (pin "1") (pinfunction "1_1") (pintype "passive"))
      (node (ref "C15") (pin "2") (pinfunction "2_2") (pintype "passive"))
      (node (ref "C16") (pin "2") (pinfunction "2_2") (pintype "passive"))
      (node (ref "C17") (pin "2") (pinfunction "2_2") (pintype "passive"))
      (node (ref "C18") (pin "2") (pinfunction "2_2") (pintype "passive"))
      (node (ref "C19") (pin "2") (pinfunction "2_2") (pintype "passive"))
      (node (ref "C2") (pin "2") (pinfunction "2_2") (pintype "passive"))
      (node (ref "C20") (pin "2") (pinfunction "2_2") (pintype "passive"))
      (node (ref "C22") (pin "2") (pinfunction "2_2") (pintype "passive"))
      (node (ref "C3") (pin "2") (pinfunction "2_2") (pintype "passive"))
      (node (ref "C4") (pin "1") (pinfunction "1_1") (pintype "passive"))
      (node (ref "C5") (pin "1") (pinfunction "1_1") (pintype "passive"))
      (node (ref "C6") (pin "2") (pinfunction "2_2") (pintype "passive"))
      (node (ref "C7") (pin "2") (pinfunction "2_2") (pintype "passive"))
      (node (ref "C8") (pin "1") (pinfunction "1_1") (pintype "passive"))
      (node (ref "Cam bien") (pin "1") (pinfunction "1_1") (pintype "passive"))
      (node (ref "ESC1") (pin "1") (pinfunction "1_1") (pintype "passive"))
      (node (ref "ESC2") (pin "1") (pinfunction "1_1") (pintype "passive"))
      (node (ref "ESC3") (pin "1") (pinfunction "1_1") (pintype "passive"))
      (node (ref "ESC4") (pin "1") (pinfunction "1_1") (pintype "passive"))
      (node (ref "GPS") (pin "1") (pinfunction "1_1") (pintype "passive"))
      (node (ref "J1") (pin "1") (pinfunction "1_1") (pintype "passive"))
      (node (ref "J2") (pin "1") (pinfunction "1_1") (pintype "passive"))
      (node (ref "J2") (pin "2") (pinfunction "2_2") (pintype "passive"))
      (node (ref "J2") (pin "5") (pinfunction "5_5") (pintype "passive"))
      (node (ref "J2") (pin "6") (pinfunction "6_6") (pintype "passive"))
      (node (ref "JP3") (pin "1") (pinfunction "1_1") (pintype "passive"))
      (node (ref "LED1") (pin "2") (pinfunction "K_2") (pintype "passive"))
      (node (ref "LED2") (pin "2") (pinfunction "2_2") (pintype "passive"))
      (node (ref "LED3") (pin "2") (pinfunction "2_2") (pintype "passive"))
      (node (ref "LED4") (pin "2") (pinfunction "2_2") (pintype "passive"))
      (node (ref "LIDAR1") (pin "1") (pinfunction "1_1") (pintype "passive"))
      (node (ref "LIDAR2") (pin "1") (pinfunction "1_1") (pintype "passive"))
      (node (ref "LIDAR3") (pin "1") (pinfunction "1_1") (pintype "passive"))
      (node (ref "MD1") (pin "1") (pinfunction "GND_1") (pintype "passive"))
      (node (ref "MIC1") (pin "3") (pinfunction "GND_3") (pintype "passive"))
      (node (ref "P1") (pin "1") (pinfunction "1_1") (pintype "passive"))
      (node (ref "Q1") (pin "1") (pinfunction "E_1") (pintype "passive"))
      (node (ref "Q2") (pin "1") (pinfunction "E_1") (pintype "passive"))
      (node (ref "R10") (pin "1") (pinfunction "1_1") (pintype "passive"))
      (node (ref "R16") (pin "1") (pinfunction "1_1") (pintype "passive"))
      (node (ref "R25") (pin "1") (pinfunction "1_1") (pintype "passive"))
      (node (ref "R3") (pin "1") (pinfunction "1_1") (pintype "passive"))
      (node (ref "R4") (pin "1") (pinfunction "1_1") (pintype "passive"))
      (node (ref "R6") (pin "1") (pinfunction "1_1") (pintype "passive"))
      (node (ref "SERVO") (pin "3") (pinfunction "3_3") (pintype "passive"))
      (node (ref "Tho1") (pin "3") (pinfunction "GND_3") (pintype "passive"))
      (node (ref "U1") (pin "1") (pinfunction "GND_1") (pintype "passive"))
    )
    (net (code "55") (name "Net-(*-BOOT0)") (class "Default")
      (node (ref "*") (pin "94") (pinfunction "BOOT0_94") (pintype "passive"))
      (node (ref "R6") (pin "2") (pinfunction "2_2") (pintype "passive"))
    )
    (net (code "56") (name "Net-(*-PB2)") (class "Default")
      (node (ref "*") (pin "37") (pinfunction "PB2_37") (pintype "passive"))
      (node (ref "R4") (pin "2") (pinfunction "2_2") (pintype "passive"))
    )
    (net (code "57") (name "Net-(*-VCAP_1)") (class "Default")
      (node (ref "*") (pin "49") (pinfunction "VCAP_1_49") (pintype "passive"))
      (node (ref "C4") (pin "2") (pinfunction "2_2") (pintype "passive"))
    )
    (net (code "58") (name "Net-(*-VCAP_2)") (class "Default")
      (node (ref "*") (pin "73") (pinfunction "VCAP_2_73") (pintype "passive"))
      (node (ref "C5") (pin "2") (pinfunction "2_2") (pintype "passive"))
    )
    (net (code "59") (name "Net-(*-VREF)") (class "Default")
      (node (ref "*") (pin "21") (pinfunction "VREF_21") (pintype "passive"))
      (node (ref "R7") (pin "1") (pinfunction "1_1") (pintype "passive"))
    )
    (net (code "60") (name "Net-(D1-A)") (class "Default")
      (node (ref "D1") (pin "1") (pinfunction "A_1") (pintype "passive"))
      (node (ref "P1") (pin "2") (pinfunction "2_2") (pintype "passive"))
    )
    (net (code "61") (name "Net-(D1-K)") (class "Default")
      (node (ref "D1") (pin "2") (pinfunction "K_2") (pintype "passive"))
      (node (ref "SW1") (pin "1") (pinfunction "COM_1") (pintype "passive"))
    )
    (net (code "62") (name "Net-(LED1-A)") (class "Default")
      (node (ref "LED1") (pin "1") (pinfunction "A_1") (pintype "passive"))
      (node (ref "R2") (pin "2") (pinfunction "2_2") (pintype "passive"))
    )
    (net (code "63") (name "Net-(LED2-Pad1)") (class "Default")
      (node (ref "LED2") (pin "1") (pinfunction "1_1") (pintype "passive"))
      (node (ref "R8") (pin "1") (pinfunction "1_1") (pintype "passive"))
    )
    (net (code "64") (name "Net-(LED3-Pad1)") (class "Default")
      (node (ref "LED3") (pin "1") (pinfunction "1_1") (pintype "passive"))
      (node (ref "R11") (pin "1") (pinfunction "1_1") (pintype "passive"))
    )
    (net (code "65") (name "Net-(LED4-Pad1)") (class "Default")
      (node (ref "LED4") (pin "1") (pinfunction "1_1") (pintype "passive"))
      (node (ref "R13") (pin "1") (pinfunction "1_1") (pintype "passive"))
    )
    (net (code "66") (name "Net-(MIC1-FB)") (class "Default")
      (node (ref "MIC1") (pin "5") (pinfunction "FB_5") (pintype "passive"))
      (node (ref "R1") (pin "1") (pinfunction "1_1") (pintype "passive"))
      (node (ref "R3") (pin "2") (pinfunction "2_2") (pintype "passive"))
    )
    (net (code "67") (name "Net-(Q1-B)") (class "Default")
      (node (ref "Q1") (pin "3") (pinfunction "B_3") (pintype "passive"))
      (node (ref "R10") (pin "2") (pinfunction "2_2") (pintype "passive"))
      (node (ref "R5") (pin "1") (pinfunction "1_1") (pintype "passive"))
    )
    (net (code "68") (name "Net-(Q1-C)") (class "Default")
      (node (ref "BZ1") (pin "2") (pinfunction "2_2") (pintype "passive"))
      (node (ref "Q1") (pin "2") (pinfunction "C_2") (pintype "passive"))
    )
    (net (code "69") (name "Net-(Q2-B)") (class "Default")
      (node (ref "Q2") (pin "3") (pinfunction "B_3") (pintype "passive"))
      (node (ref "R19") (pin "1") (pinfunction "1_1") (pintype "passive"))
      (node (ref "R25") (pin "2") (pinfunction "2_2") (pintype "passive"))
    )
    (net (code "70") (name "Net-(Q2-C)") (class "Default")
      (node (ref "Q2") (pin "2") (pinfunction "C_2") (pintype "passive"))
      (node (ref "R24") (pin "1") (pinfunction "1_1") (pintype "passive"))
      (node (ref "SERVO") (pin "2") (pinfunction "2_2") (pintype "passive"))
    )
    (net (code "71") (name "VIN") (class "Default")
      (node (ref "C2") (pin "1") (pinfunction "1_1") (pintype "passive"))
      (node (ref "MIC1") (pin "1") (pinfunction "ON/OFF_1") (pintype "passive"))
      (node (ref "MIC1") (pin "2") (pinfunction "VIN_2") (pintype "passive"))
      (node (ref "R15") (pin "2") (pinfunction "2_2") (pintype "passive"))
      (node (ref "SW1") (pin "2") (pinfunction "NC_2") (pintype "passive"))
      (node (ref "TP1") (pin "1") (pinfunction "1_1") (pintype "passive"))
    )
    (net (code "72") (name "unconnected-(*-PA3-Pad26)") (class "Default")
      (node (ref "*") (pin "26") (pinfunction "PA3_26") (pintype "passive+no_connect"))
    )
    (net (code "73") (name "unconnected-(*-PA8-Pad67)") (class "Default")
      (node (ref "*") (pin "67") (pinfunction "PA8_67") (pintype "passive+no_connect"))
    )
    (net (code "74") (name "unconnected-(*-PA12-Pad71)") (class "Default")
      (node (ref "*") (pin "71") (pinfunction "PA12_71") (pintype "passive+no_connect"))
    )
    (net (code "75") (name "unconnected-(*-PB0-Pad35)") (class "Default")
      (node (ref "*") (pin "35") (pinfunction "PB0_35") (pintype "passive+no_connect"))
    )
    (net (code "76") (name "unconnected-(*-PB1-Pad36)") (class "Default")
      (node (ref "*") (pin "36") (pinfunction "PB1_36") (pintype "passive+no_connect"))
    )
    (net (code "77") (name "unconnected-(*-PB3-Pad89)") (class "Default")
      (node (ref "*") (pin "89") (pinfunction "PB3_89") (pintype "passive+no_connect"))
    )
    (net (code "78") (name "unconnected-(*-PB4-Pad90)") (class "Default")
      (node (ref "*") (pin "90") (pinfunction "PB4_90") (pintype "passive+no_connect"))
    )
    (net (code "79") (name "unconnected-(*-PB5-Pad91)") (class "Default")
      (node (ref "*") (pin "91") (pinfunction "PB5_91") (pintype "passive+no_connect"))
    )
    (net (code "80") (name "unconnected-(*-PB9-Pad96)") (class "Default")
      (node (ref "*") (pin "96") (pinfunction "PB9_96") (pintype "passive+no_connect"))
    )
    (net (code "81") (name "unconnected-(*-PB12-Pad51)") (class "Default")
      (node (ref "*") (pin "51") (pinfunction "PB12_51") (pintype "passive+no_connect"))
    )
    (net (code "82") (name "unconnected-(*-PB13-Pad52)") (class "Default")
      (node (ref "*") (pin "52") (pinfunction "PB13_52") (pintype "passive+no_connect"))
    )
    (net (code "83") (name "unconnected-(*-PB14-Pad53)") (class "Default")
      (node (ref "*") (pin "53") (pinfunction "PB14_53") (pintype "passive+no_connect"))
    )
    (net (code "84") (name "unconnected-(*-PB15-Pad54)") (class "Default")
      (node (ref "*") (pin "54") (pinfunction "PB15_54") (pintype "passive+no_connect"))
    )
    (net (code "85") (name "unconnected-(*-PC1-Pad16)") (class "Default")
      (node (ref "*") (pin "16") (pinfunction "PC1_16") (pintype "passive+no_connect"))
    )
    (net (code "86") (name "unconnected-(*-PC2-Pad17)") (class "Default")
      (node (ref "*") (pin "17") (pinfunction "PC2_17") (pintype "passive+no_connect"))
    )
    (net (code "87") (name "unconnected-(*-PC3-Pad18)") (class "Default")
      (node (ref "*") (pin "18") (pinfunction "PC3_18") (pintype "passive+no_connect"))
    )
    (net (code "88") (name "unconnected-(*-PC13-Pad7)") (class "Default")
      (node (ref "*") (pin "7") (pinfunction "PC13_7") (pintype "passive+no_connect"))
    )
    (net (code "89") (name "unconnected-(*-PD3-Pad84)") (class "Default")
      (node (ref "*") (pin "84") (pinfunction "PD3_84") (pintype "passive+no_connect"))
    )
    (net (code "90") (name "unconnected-(*-PD4-Pad85)") (class "Default")
      (node (ref "*") (pin "85") (pinfunction "PD4_85") (pintype "passive+no_connect"))
    )
    (net (code "91") (name "unconnected-(*-PD5-Pad86)") (class "Default")
      (node (ref "*") (pin "86") (pinfunction "PD5_86") (pintype "passive+no_connect"))
    )
    (net (code "92") (name "unconnected-(*-PD6-Pad87)") (class "Default")
      (node (ref "*") (pin "87") (pinfunction "PD6_87") (pintype "passive+no_connect"))
    )
    (net (code "93") (name "unconnected-(*-PD7-Pad88)") (class "Default")
      (node (ref "*") (pin "88") (pinfunction "PD7_88") (pintype "passive+no_connect"))
    )
    (net (code "94") (name "unconnected-(*-PD10-Pad57)") (class "Default")
      (node (ref "*") (pin "57") (pinfunction "PD10_57") (pintype "passive+no_connect"))
    )
    (net (code "95") (name "unconnected-(*-PD11-Pad58)") (class "Default")
      (node (ref "*") (pin "58") (pinfunction "PD11_58") (pintype "passive+no_connect"))
    )
    (net (code "96") (name "unconnected-(*-PE0-Pad97)") (class "Default")
      (node (ref "*") (pin "97") (pinfunction "PE0_97") (pintype "passive+no_connect"))
    )
    (net (code "97") (name "unconnected-(*-PE1-Pad98)") (class "Default")
      (node (ref "*") (pin "98") (pinfunction "PE1_98") (pintype "passive+no_connect"))
    )
    (net (code "98") (name "unconnected-(*-PE2-Pad1)") (class "Default")
      (node (ref "*") (pin "1") (pinfunction "PE2_1") (pintype "passive+no_connect"))
    )
    (net (code "99") (name "unconnected-(*-PE3-Pad2)") (class "Default")
      (node (ref "*") (pin "2") (pinfunction "PE3_2") (pintype "passive+no_connect"))
    )
    (net (code "100") (name "unconnected-(*-PE4-Pad3)") (class "Default")
      (node (ref "*") (pin "3") (pinfunction "PE4_3") (pintype "passive+no_connect"))
    )
    (net (code "101") (name "unconnected-(*-PE5-Pad4)") (class "Default")
      (node (ref "*") (pin "4") (pinfunction "PE5_4") (pintype "passive+no_connect"))
    )
    (net (code "102") (name "unconnected-(*-PE6-Pad5)") (class "Default")
      (node (ref "*") (pin "5") (pinfunction "PE6_5") (pintype "passive+no_connect"))
    )
    (net (code "103") (name "unconnected-(SW1-NO-Pad3)") (class "Default")
      (node (ref "SW1") (pin "3") (pinfunction "NO_3") (pintype "passive"))
    )
    (net (code "104") (name "unconnected-(Tho1-3V3-Pad2)") (class "Default")
      (node (ref "Tho1") (pin "2") (pinfunction "3V3_2") (pintype "passive+no_connect"))
    )
    (net (code "105") (name "unconnected-(VIT1-1-PadVIT1)") (class "Default")
      (node (ref "VIT1") (pin "VIT1") (pinfunction "1_VIT1") (pintype "passive"))
    )
    (net (code "106") (name "unconnected-(VIT2-1-PadVIT1)") (class "Default")
      (node (ref "VIT2") (pin "VIT1") (pinfunction "1_VIT1") (pintype "passive"))
    )
    (net (code "107") (name "unconnected-(VIT3-1-PadVIT1)") (class "Default")
      (node (ref "VIT3") (pin "VIT1") (pinfunction "1_VIT1") (pintype "passive"))
    )
    (net (code "108") (name "unconnected-(VIT4-1-PadVIT1)") (class "Default")
      (node (ref "VIT4") (pin "VIT1") (pinfunction "1_VIT1") (pintype "passive"))
    )
  )
)
